# og20_rev2.net
KiCad netlist of a schematic drawn in EAGLE
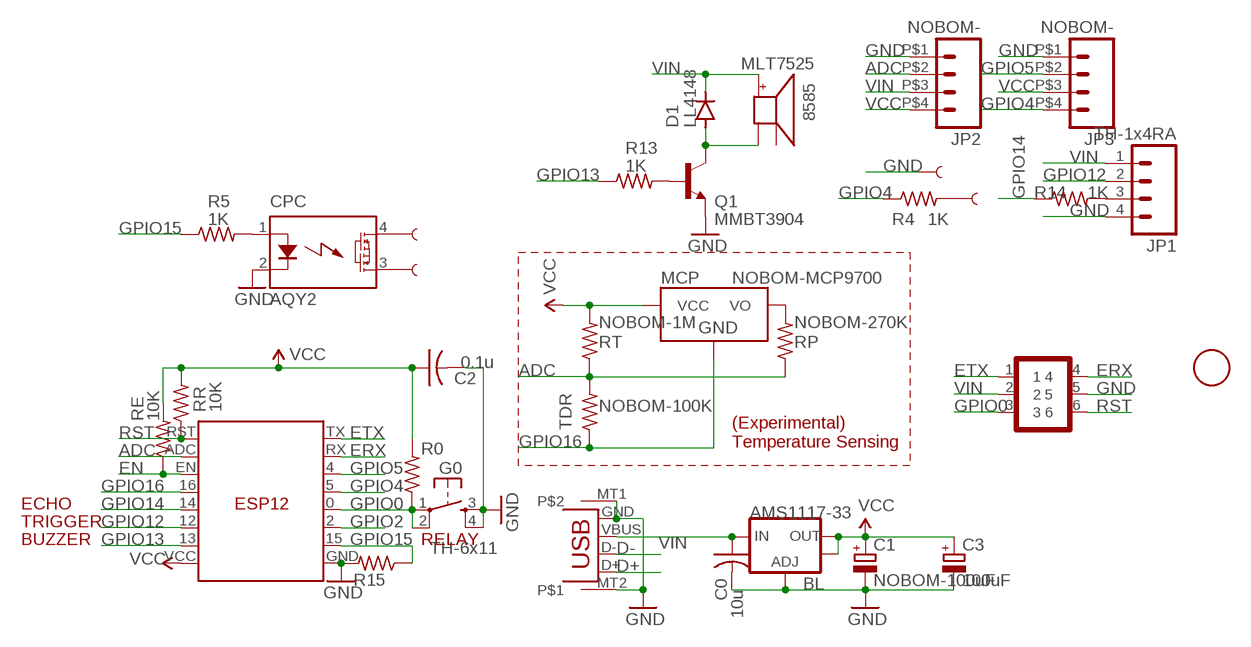
[diagram p0: schematic, sheet 1]

(export (version "E")
  (design (tool "Eeschema 10.0.6"))
  (components
    (comp (ref "0F")
      (value "FIDUCIAL")
      (footprint "eagle-import:FIDUCIAL_1MM")
      (libsource (lib "eagle-import") (part "FIDUCIAL"))
    )
    (comp (ref "8585")
      (value "MLT7525")
      (footprint "eagle-import:SMT-8585-BUZZER")
      (libsource (lib "eagle-import") (part "BUZZER"))
    )
    (comp (ref "BL")
      (value "AMS1117-33")
      (footprint "eagle-import:SOT223")
      (libsource (lib "eagle-import") (part "V_REG_LM1117SOT223"))
    )
    (comp (ref "C0")
      (value "10u")
      (footprint "eagle-import:C0805K")
      (libsource (lib "eagle-import") (part "C-USC0805K"))
    )
    (comp (ref "C1")
      (value "NOBOM-100uF")
      (footprint "eagle-import:B_3528-21R")
      (libsource (lib "eagle-import") (part "CPOL-EUB/3528-21R"))
    )
    (comp (ref "C2")
      (value "0.1u")
      (footprint "eagle-import:C0603K")
      (libsource (lib "eagle-import") (part "C-USC0603K"))
    )
    (comp (ref "C3")
      (value "100uF")
      (footprint "eagle-import:PANASONIC_C")
      (libsource (lib "eagle-import") (part "CPOL-EUC"))
    )
    (comp (ref "CPC")
      (value "AQY2")
      (footprint "eagle-import:PHOTOMOS")
      (libsource (lib "eagle-import") (part "AQY282"))
    )
    (comp (ref "D1")
      (value "LL4148")
      (footprint "eagle-import:MINIMELF")
      (libsource (lib "eagle-import") (part "DIODE-MINIMELF"))
    )
    (comp (ref "ESP")
      (value "ESP8266")
      (footprint "eagle-import:ESP12")
      (libsource (lib "eagle-import") (part "ESP12"))
    )
    (comp (ref "G0")
      (value "TH-6x11")
      (footprint "eagle-import:TACTILE-PTH")
      (libsource (lib "eagle-import") (part "TAC_SWITCHPTH"))
    )
    (comp (ref "JP1")
      (value "TH-1x4RA")
      (footprint "eagle-import:1X04_SONICSENSOR_EXT2")
      (libsource (lib "eagle-import") (part "M04EXT2"))
    )
    (comp (ref "JP2")
      (value "NOBOM-")
      (footprint "eagle-import:1X04-2X2")
      (libsource (lib "eagle-import") (part "M042X2"))
    )
    (comp (ref "JP3")
      (value "NOBOM-")
      (footprint "eagle-import:1X04-2X2")
      (libsource (lib "eagle-import") (part "M042X2"))
    )
    (comp (ref "MCP")
      (value "NOBOM-MCP9700")
      (footprint "eagle-import:SOT23-3")
      (libsource (lib "eagle-import") (part "MCP9700SMD"))
    )
    (comp (ref "Q1")
      (value "MMBT3904")
      (footprint "eagle-import:SOT23-3")
      (libsource (lib "eagle-import") (part "TRANSISTOR_NPNSOT23-3"))
    )
    (comp (ref "R0")
      (value "10K")
      (footprint "eagle-import:R0603")
      (libsource (lib "eagle-import") (part "adafruit (picker 的冲突副本 2014-10-29)_R-US_R0603"))
    )
    (comp (ref "R4")
      (value "1K")
      (footprint "eagle-import:R0603")
      (libsource (lib "eagle-import") (part "adafruit2013_R-US_R0603"))
    )
    (comp (ref "R5")
      (value "1K")
      (footprint "eagle-import:R0603")
      (libsource (lib "eagle-import") (part "adafruit2013_R-US_R0603"))
    )
    (comp (ref "R13")
      (value "1K")
      (footprint "eagle-import:R0603")
      (libsource (lib "eagle-import") (part "adafruit2013_R-US_R0603"))
    )
    (comp (ref "R14")
      (value "1K")
      (footprint "eagle-import:R0603")
      (libsource (lib "eagle-import") (part "adafruit2013_R-US_R0603"))
    )
    (comp (ref "R15")
      (value "10K")
      (footprint "eagle-import:R0603")
      (libsource (lib "eagle-import") (part "adafruit (picker 的冲突副本 2014-10-29)_R-US_R0603"))
    )
    (comp (ref "RE")
      (value "10K")
      (footprint "eagle-import:R0603")
      (libsource (lib "eagle-import") (part "adafruit (picker 的冲突副本 2014-10-29)_R-US_R0603"))
    )
    (comp (ref "RP")
      (value "NOBOM-270K")
      (footprint "eagle-import:R0603")
      (libsource (lib "eagle-import") (part "adafruit (picker 的冲突副本 2014-10-29)_R-US_R0603"))
    )
    (comp (ref "RR")
      (value "10K")
      (footprint "eagle-import:R0603")
      (libsource (lib "eagle-import") (part "adafruit (picker 的冲突副本 2014-10-29)_R-US_R0603"))
    )
    (comp (ref "RT")
      (value "NOBOM-1M")
      (footprint "eagle-import:R0603")
      (libsource (lib "eagle-import") (part "adafruit (picker 的冲突副本 2014-10-29)_R-US_R0603"))
    )
    (comp (ref "TDR")
      (value "NOBOM-100K")
      (footprint "eagle-import:R0805")
      (libsource (lib "eagle-import") (part "R-US_R0805"))
    )
    (comp (ref "U$1")
      (value "NOBOM-GF2x3")
      (footprint "eagle-import:GOLDFINGER_2X3")
      (libsource (lib "eagle-import") (part "GOLDFINGER_2X3"))
    )
    (comp (ref "U$2")
      (value "NOBOM-")
      (footprint "eagle-import:PETAL-3MM-1SIDE")
      (libsource (lib "eagle-import") (part "SEWTAP3MM-1SIDE"))
    )
    (comp (ref "U$3")
      (value "NOBOM-")
      (footprint "eagle-import:PETAL-3MM-1SIDE")
      (libsource (lib "eagle-import") (part "SEWTAP3MM-1SIDE"))
    )
    (comp (ref "U$4")
      (value "NOBOM-")
      (footprint "eagle-import:PETAL-3MM-1SIDE")
      (libsource (lib "eagle-import") (part "SEWTAP3MM-1SIDE"))
    )
    (comp (ref "U$5")
      (value "NOBOM-")
      (footprint "eagle-import:PETAL-3MM-1SIDE")
      (libsource (lib "eagle-import") (part "SEWTAP3MM-1SIDE"))
    )
    (comp (ref "X3")
      (value "MICROXNJ")
      (footprint "eagle-import:USB-MICROB2")
      (libsource (lib "eagle-import") (part "USB+GND"))
    )
  )
  (nets
    (net (code "1") (name "/ADC") (class "Default")
      (node (ref "ESP") (pin "ADC") (pinfunction "ADC_ADC") (pintype "bidirectional"))
      (node (ref "JP2") (pin "P$2") (pinfunction "2_P$2") (pintype "passive"))
      (node (ref "RP") (pin "1") (pinfunction "1_1") (pintype "passive"))
      (node (ref "RT") (pin "1") (pinfunction "1_1") (pintype "passive"))
      (node (ref "TDR") (pin "2") (pinfunction "2_2") (pintype "passive"))
    )
    (net (code "2") (name "/D+") (class "Default")
      (node (ref "X3") (pin "D+") (pinfunction "D+_D+") (pintype "bidirectional"))
    )
    (net (code "3") (name "/D-") (class "Default")
      (node (ref "X3") (pin "D-") (pinfunction "D-_D-") (pintype "bidirectional"))
    )
    (net (code "4") (name "/EN") (class "Default")
      (node (ref "ESP") (pin "EN") (pinfunction "EN_EN") (pintype "bidirectional"))
      (node (ref "RE") (pin "1") (pinfunction "1_1") (pintype "passive"))
    )
    (net (code "5") (name "/ERX") (class "Default")
      (node (ref "ESP") (pin "RX") (pinfunction "RX_RX") (pintype "bidirectional"))
      (node (ref "U$1") (pin "4") (pinfunction "4_4") (pintype "bidirectional"))
    )
    (net (code "6") (name "/ETX") (class "Default")
      (node (ref "ESP") (pin "TX") (pinfunction "TX_TX") (pintype "bidirectional"))
      (node (ref "U$1") (pin "1") (pinfunction "1_1") (pintype "bidirectional"))
    )
    (net (code "7") (name "/GPIO0") (class "Default")
      (node (ref "ESP") (pin "0") (pinfunction "G0_0") (pintype "bidirectional"))
      (node (ref "G0") (pin "1") (pinfunction "1_1") (pintype "passive"))
      (node (ref "G0") (pin "2") (pinfunction "2_2") (pintype "passive"))
      (node (ref "R0") (pin "1") (pinfunction "1_1") (pintype "passive"))
      (node (ref "U$1") (pin "3") (pinfunction "3_3") (pintype "bidirectional"))
    )
    (net (code "8") (name "/GPIO2") (class "Default")
      (node (ref "ESP") (pin "2") (pinfunction "G2_2") (pintype "bidirectional"))
    )
    (net (code "9") (name "/GPIO4") (class "Default")
      (node (ref "ESP") (pin "5") (pinfunction "G5_5") (pintype "bidirectional"))
      (node (ref "JP3") (pin "P$4") (pinfunction "4_P$4") (pintype "passive"))
      (node (ref "R4") (pin "1") (pinfunction "1_1") (pintype "passive"))
    )
    (net (code "10") (name "/GPIO5") (class "Default")
      (node (ref "ESP") (pin "4") (pinfunction "G4_4") (pintype "bidirectional"))
      (node (ref "JP3") (pin "P$2") (pinfunction "2_P$2") (pintype "passive"))
    )
    (net (code "11") (name "/GPIO12") (class "Default")
      (node (ref "ESP") (pin "12") (pinfunction "G12_12") (pintype "bidirectional"))
      (node (ref "JP1") (pin "2") (pinfunction "2_2") (pintype "passive"))
    )
    (net (code "12") (name "/GPIO13") (class "Default")
      (node (ref "ESP") (pin "13") (pinfunction "G13_13") (pintype "bidirectional"))
      (node (ref "R13") (pin "1") (pinfunction "1_1") (pintype "passive"))
    )
    (net (code "13") (name "/GPIO14") (class "Default")
      (node (ref "ESP") (pin "14") (pinfunction "G14_14") (pintype "bidirectional"))
      (node (ref "R14") (pin "1") (pinfunction "1_1") (pintype "passive"))
    )
    (net (code "14") (name "/GPIO15") (class "Default")
      (node (ref "ESP") (pin "15") (pinfunction "G15_15") (pintype "bidirectional"))
      (node (ref "R15") (pin "1") (pinfunction "1_1") (pintype "passive"))
      (node (ref "R5") (pin "1") (pinfunction "1_1") (pintype "passive"))
    )
    (net (code "15") (name "/GPIO16") (class "Default")
      (node (ref "ESP") (pin "16") (pinfunction "G16_16") (pintype "bidirectional"))
      (node (ref "MCP") (pin "3") (pinfunction "GND_3") (pintype "bidirectional"))
      (node (ref "TDR") (pin "1") (pinfunction "1_1") (pintype "passive"))
    )
    (net (code "16") (name "/RST") (class "Default")
      (node (ref "ESP") (pin "RST") (pinfunction "RST_RST") (pintype "bidirectional"))
      (node (ref "RR") (pin "1") (pinfunction "1_1") (pintype "passive"))
      (node (ref "U$1") (pin "6") (pinfunction "6_6") (pintype "bidirectional"))
    )
    (net (code "17") (name "/VIN") (class "Default")
      (node (ref "8585") (pin "+") (pinfunction "+_+") (pintype "passive"))
      (node (ref "BL") (pin "3") (pinfunction "IN_3") (pintype "input"))
      (node (ref "C0") (pin "1") (pinfunction "1_1") (pintype "passive"))
      (node (ref "D1") (pin "C") (pinfunction "C_C") (pintype "passive"))
      (node (ref "JP1") (pin "1") (pinfunction "1_1") (pintype "passive"))
      (node (ref "JP2") (pin "P$3") (pinfunction "3_P$3") (pintype "passive"))
      (node (ref "U$1") (pin "2") (pinfunction "2_2") (pintype "bidirectional"))
      (node (ref "X3") (pin "VBUS") (pinfunction "VBUS_VBUS") (pintype "bidirectional"))
    )
    (net (code "18") (name "GND") (class "Default")
      (node (ref "BL") (pin "1") (pinfunction "ADJ_1") (pintype "input"))
      (node (ref "C0") (pin "2") (pinfunction "2_2") (pintype "passive"))
      (node (ref "C1") (pin "-") (pinfunction "-_-") (pintype "passive"))
      (node (ref "C2") (pin "2") (pinfunction "2_2") (pintype "passive"))
      (node (ref "C3") (pin "-") (pinfunction "-_-") (pintype "passive"))
      (node (ref "CPC") (pin "2") (pinfunction "K_2") (pintype "passive"))
      (node (ref "ESP") (pin "GND") (pinfunction "GND_GND") (pintype "power_in"))
      (node (ref "G0") (pin "3") (pinfunction "3_3") (pintype "passive"))
      (node (ref "G0") (pin "4") (pinfunction "4_4") (pintype "passive"))
      (node (ref "JP1") (pin "4") (pinfunction "4_4") (pintype "passive"))
      (node (ref "JP2") (pin "P$1") (pinfunction "1_P$1") (pintype "passive"))
      (node (ref "JP3") (pin "P$1") (pinfunction "1_P$1") (pintype "passive"))
      (node (ref "Q1") (pin "2") (pinfunction "E_2") (pintype "passive"))
      (node (ref "R15") (pin "2") (pinfunction "2_2") (pintype "passive"))
      (node (ref "U$1") (pin "5") (pinfunction "5_5") (pintype "bidirectional"))
      (node (ref "U$4") (pin "P$1") (pinfunction "1_P$1") (pintype "bidirectional"))
      (node (ref "X3") (pin "GND") (pinfunction "GND_GND") (pintype "bidirectional"))
      (node (ref "X3") (pin "MT1") (pinfunction "P$2_MT1") (pintype "bidirectional"))
      (node (ref "X3") (pin "MT2") (pinfunction "P$1_MT2") (pintype "bidirectional"))
    )
    (net (code "19") (name "Net-(CPC-A)") (class "Default")
      (node (ref "CPC") (pin "1") (pinfunction "A_1") (pintype "passive"))
      (node (ref "R5") (pin "2") (pinfunction "2_2") (pintype "passive"))
    )
    (net (code "20") (name "Net-(CPC-DS1)") (class "Default")
      (node (ref "CPC") (pin "4") (pinfunction "DS1_4") (pintype "passive"))
      (node (ref "U$2") (pin "P$1") (pinfunction "1_P$1") (pintype "bidirectional"))
    )
    (net (code "21") (name "Net-(CPC-DS2)") (class "Default")
      (node (ref "CPC") (pin "3") (pinfunction "DS2_3") (pintype "passive"))
      (node (ref "U$3") (pin "P$1") (pinfunction "1_P$1") (pintype "bidirectional"))
    )
    (net (code "22") (name "Net-(JP1-Pad3)") (class "Default")
      (node (ref "JP1") (pin "3") (pinfunction "3_3") (pintype "passive"))
      (node (ref "R14") (pin "2") (pinfunction "2_2") (pintype "passive"))
    )
    (net (code "23") (name "Net-(MCP-VO)") (class "Default")
      (node (ref "MCP") (pin "2") (pinfunction "VO_2") (pintype "bidirectional"))
      (node (ref "RP") (pin "2") (pinfunction "2_2") (pintype "passive"))
    )
    (net (code "24") (name "Net-(Q1-B)") (class "Default")
      (node (ref "Q1") (pin "1") (pinfunction "B_1") (pintype "passive"))
      (node (ref "R13") (pin "2") (pinfunction "2_2") (pintype "passive"))
    )
    (net (code "25") (name "Net-(Q1-C)") (class "Default")
      (node (ref "8585") (pin "-") (pinfunction "-_-") (pintype "passive"))
      (node (ref "D1") (pin "A") (pinfunction "A_A") (pintype "passive"))
      (node (ref "Q1") (pin "3") (pinfunction "C_3") (pintype "passive"))
    )
    (net (code "26") (name "Net-(U$5-1)") (class "Default")
      (node (ref "R4") (pin "2") (pinfunction "2_2") (pintype "passive"))
      (node (ref "U$5") (pin "P$1") (pinfunction "1_P$1") (pintype "bidirectional"))
    )
    (net (code "27") (name "VCC") (class "Default")
      (node (ref "BL") (pin "2") (pinfunction "OUT_2") (pintype "bidirectional"))
      (node (ref "BL") (pin "4") (pinfunction "OUT_4") (pintype "bidirectional"))
      (node (ref "C1") (pin "+") (pinfunction "+_+") (pintype "passive"))
      (node (ref "C2") (pin "1") (pinfunction "1_1") (pintype "passive"))
      (node (ref "C3") (pin "+") (pinfunction "+_+") (pintype "passive"))
      (node (ref "ESP") (pin "VCC") (pinfunction "VCC_VCC") (pintype "power_in"))
      (node (ref "JP2") (pin "P$4") (pinfunction "4_P$4") (pintype "passive"))
      (node (ref "JP3") (pin "P$3") (pinfunction "3_P$3") (pintype "passive"))
      (node (ref "MCP") (pin "1") (pinfunction "VCC_1") (pintype "bidirectional"))
      (node (ref "R0") (pin "2") (pinfunction "2_2") (pintype "passive"))
      (node (ref "RE") (pin "2") (pinfunction "2_2") (pintype "passive"))
      (node (ref "RR") (pin "2") (pinfunction "2_2") (pintype "passive"))
      (node (ref "RT") (pin "2") (pinfunction "2_2") (pintype "passive"))
    )
    (net (code "28") (name "unconnected-(8585-PadA-)") (class "Default")
      (node (ref "8585") (pin "A-") (pinfunction "A-_A-") (pintype "passive"))
    )
  )
)
